# powerswitch.net
KiCad netlist of a schematic drawn in Altium Designer
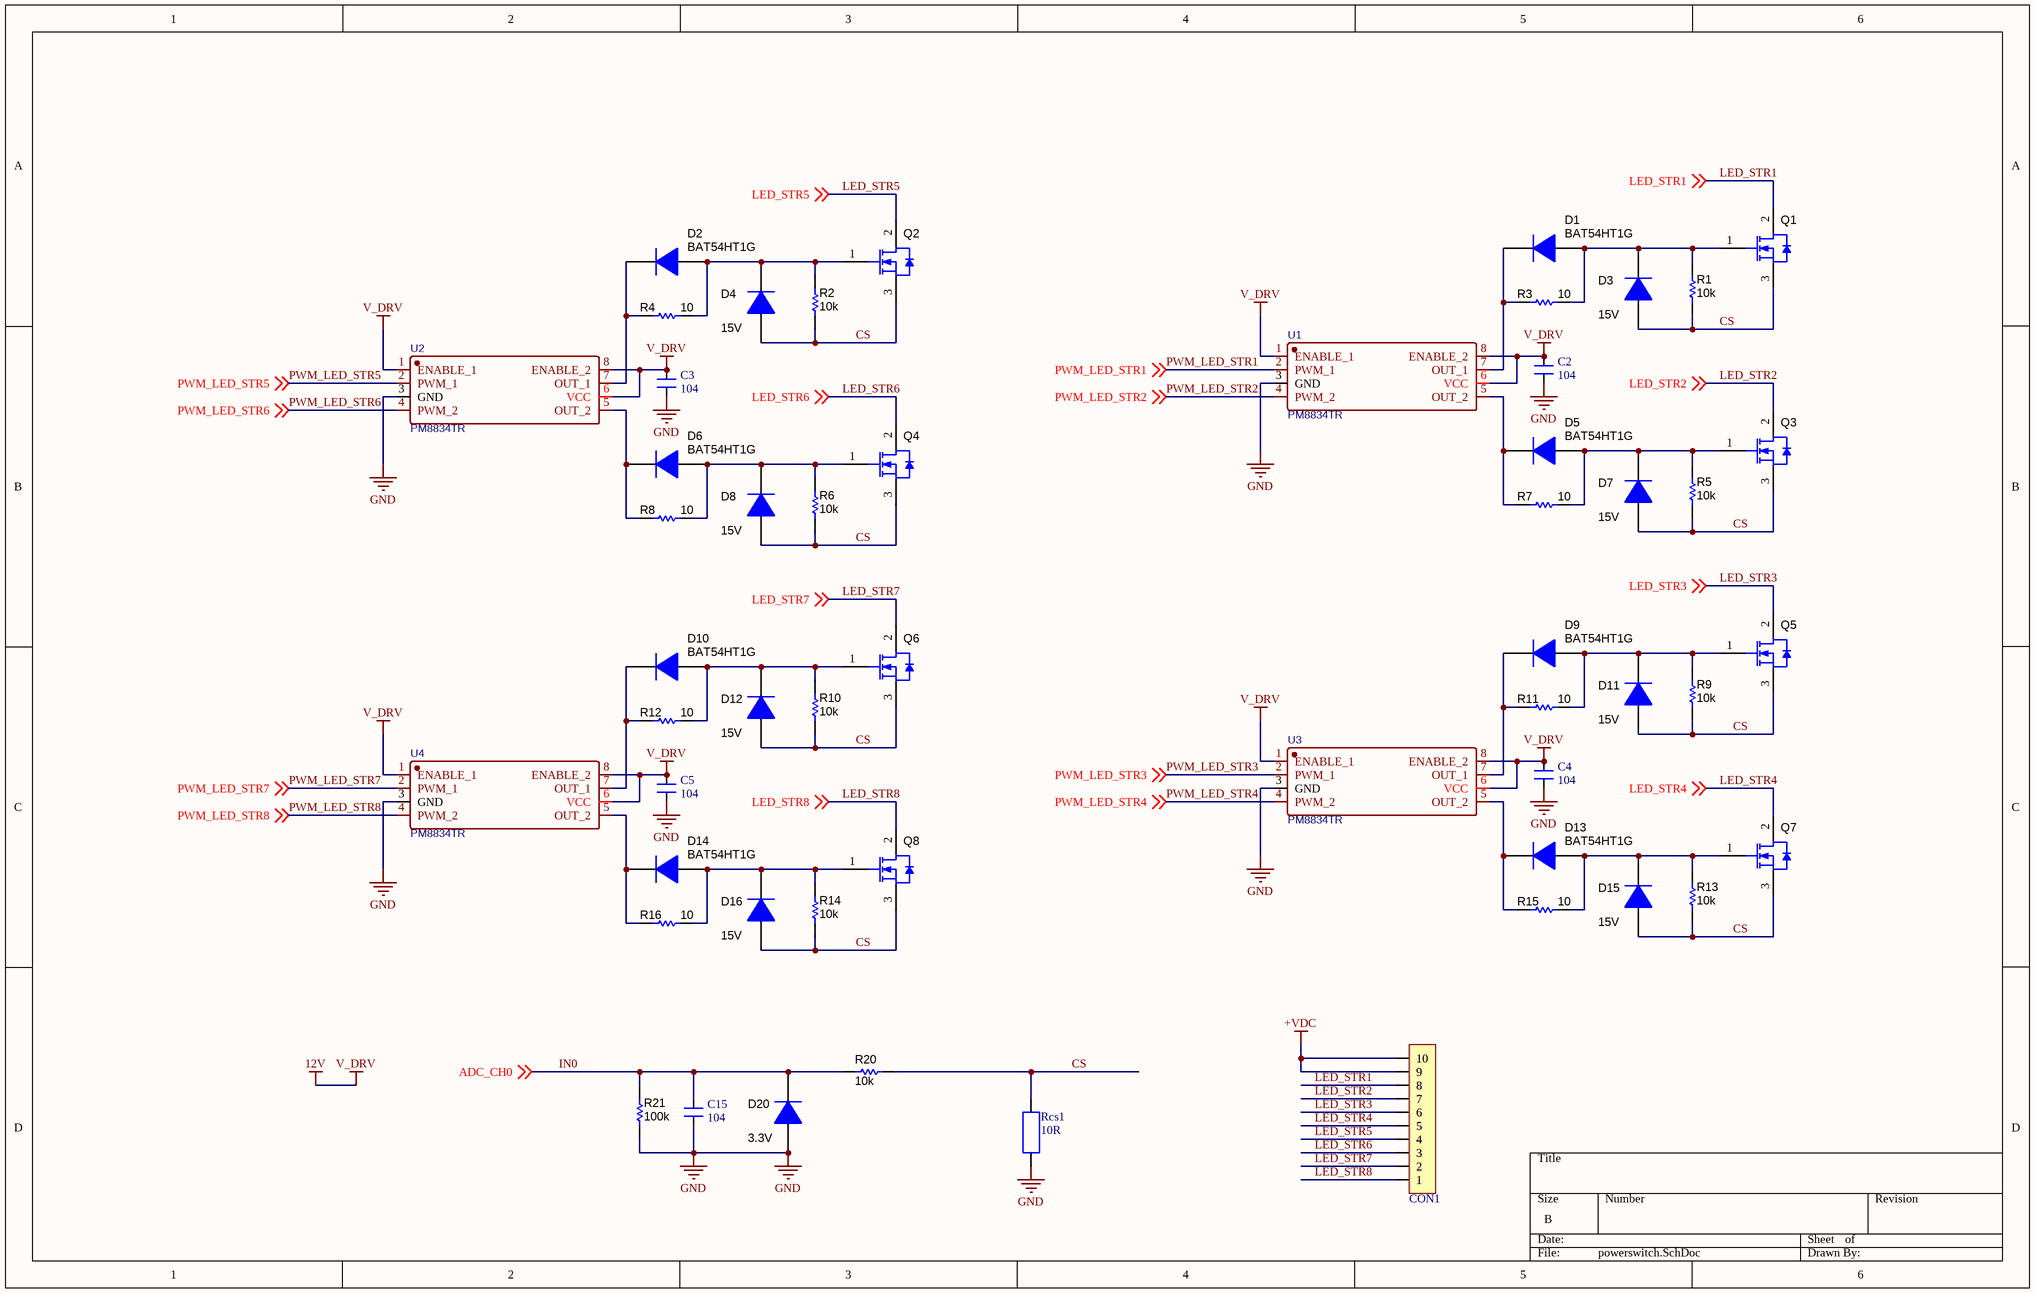
[diagram p0: powerswitch.SchDoc]

(export (version "E")
  (design (tool "Eeschema 10.0.6"))
  (components
    (comp (ref "C2")
      (value "104")
      (footprint "0805_HV")
      (description "Cap SMD")
      (libsource (lib "hatcatbietbay") (part "CM"))
    )
    (comp (ref "C3")
      (value "104")
      (footprint "0805_HV")
      (description "Cap SMD")
      (libsource (lib "hatcatbietbay") (part "CM"))
    )
    (comp (ref "C4")
      (value "104")
      (footprint "0805_HV")
      (description "Cap SMD")
      (libsource (lib "hatcatbietbay") (part "CM"))
    )
    (comp (ref "C5")
      (value "104")
      (footprint "0805_HV")
      (description "Cap SMD")
      (libsource (lib "hatcatbietbay") (part "CM"))
    )
    (comp (ref "C15")
      (value "104")
      (footprint "0805_HV")
      (description "Cap SMD")
      (libsource (lib "hatcatbietbay") (part "CM"))
    )
    (comp (ref "CON1")
      (value "CON 10 EDG 5.08_MH")
      (footprint "Con 10 EDG 5.08")
      (description "CON 10 EDG 5.08 (xanh cong)")
      (libsource (lib "MH_DA_THU_VIEN_16122016") (part "CON 10 EDG 5.08_MH"))
    )
    (comp (ref "D1")
      (value "BAT54HT1G")
      (footprint "SOD-323")
      (description "Diode, Switching, 100 V, 0.2 A, SOD-323")
      (fields
        (field (name "MANUFACTURER") "Micro Commercial Components")
        (field (name "PUBLISHER") "Texas Instruments")
      )
      (libsource (lib "Diode") (part "MMDL914-TP"))
    )
    (comp (ref "D2")
      (value "BAT54HT1G")
      (footprint "SOD-323")
      (description "Diode, Switching, 100 V, 0.2 A, SOD-323")
      (fields
        (field (name "MANUFACTURER") "Micro Commercial Components")
        (field (name "PUBLISHER") "Texas Instruments")
      )
      (libsource (lib "Diode") (part "MMDL914-TP"))
    )
    (comp (ref "D3")
      (value "15V")
      (footprint "SOD-323")
      (description "Diode, Switching, 100 V, 0.2 A, SOD-323")
      (fields
        (field (name "PARTNUMBER") "BAV21W-7-F")
        (field (name "MANUFACTURER") "Micro Commercial Components")
        (field (name "PUBLISHER") "Texas Instruments")
      )
      (libsource (lib "Diode") (part "MMDL914-TP"))
    )
    (comp (ref "D4")
      (value "15V")
      (footprint "SOD-323")
      (description "Diode, Switching, 100 V, 0.2 A, SOD-323")
      (fields
        (field (name "PARTNUMBER") "BAV21W-7-F")
        (field (name "MANUFACTURER") "Micro Commercial Components")
        (field (name "PUBLISHER") "Texas Instruments")
      )
      (libsource (lib "Diode") (part "MMDL914-TP"))
    )
    (comp (ref "D5")
      (value "BAT54HT1G")
      (footprint "SOD-323")
      (description "Diode, Switching, 100 V, 0.2 A, SOD-323")
      (fields
        (field (name "MANUFACTURER") "Micro Commercial Components")
        (field (name "PUBLISHER") "Texas Instruments")
      )
      (libsource (lib "Diode") (part "MMDL914-TP"))
    )
    (comp (ref "D6")
      (value "BAT54HT1G")
      (footprint "SOD-323")
      (description "Diode, Switching, 100 V, 0.2 A, SOD-323")
      (fields
        (field (name "MANUFACTURER") "Micro Commercial Components")
        (field (name "PUBLISHER") "Texas Instruments")
      )
      (libsource (lib "Diode") (part "MMDL914-TP"))
    )
    (comp (ref "D7")
      (value "15V")
      (footprint "SOD-323")
      (description "Diode, Switching, 100 V, 0.2 A, SOD-323")
      (fields
        (field (name "PARTNUMBER") "BAV21W-7-F")
        (field (name "MANUFACTURER") "Micro Commercial Components")
        (field (name "PUBLISHER") "Texas Instruments")
      )
      (libsource (lib "Diode") (part "MMDL914-TP"))
    )
    (comp (ref "D8")
      (value "15V")
      (footprint "SOD-323")
      (description "Diode, Switching, 100 V, 0.2 A, SOD-323")
      (fields
        (field (name "PARTNUMBER") "BAV21W-7-F")
        (field (name "MANUFACTURER") "Micro Commercial Components")
        (field (name "PUBLISHER") "Texas Instruments")
      )
      (libsource (lib "Diode") (part "MMDL914-TP"))
    )
    (comp (ref "D9")
      (value "BAT54HT1G")
      (footprint "SOD-323")
      (description "Diode, Switching, 100 V, 0.2 A, SOD-323")
      (fields
        (field (name "MANUFACTURER") "Micro Commercial Components")
        (field (name "PUBLISHER") "Texas Instruments")
      )
      (libsource (lib "Diode") (part "MMDL914-TP"))
    )
    (comp (ref "D10")
      (value "BAT54HT1G")
      (footprint "SOD-323")
      (description "Diode, Switching, 100 V, 0.2 A, SOD-323")
      (fields
        (field (name "MANUFACTURER") "Micro Commercial Components")
        (field (name "PUBLISHER") "Texas Instruments")
      )
      (libsource (lib "Diode") (part "MMDL914-TP"))
    )
    (comp (ref "D11")
      (value "15V")
      (footprint "SOD-323")
      (description "Diode, Switching, 100 V, 0.2 A, SOD-323")
      (fields
        (field (name "PARTNUMBER") "BAV21W-7-F")
        (field (name "MANUFACTURER") "Micro Commercial Components")
        (field (name "PUBLISHER") "Texas Instruments")
      )
      (libsource (lib "Diode") (part "MMDL914-TP"))
    )
    (comp (ref "D12")
      (value "15V")
      (footprint "SOD-323")
      (description "Diode, Switching, 100 V, 0.2 A, SOD-323")
      (fields
        (field (name "PARTNUMBER") "BAV21W-7-F")
        (field (name "MANUFACTURER") "Micro Commercial Components")
        (field (name "PUBLISHER") "Texas Instruments")
      )
      (libsource (lib "Diode") (part "MMDL914-TP"))
    )
    (comp (ref "D13")
      (value "BAT54HT1G")
      (footprint "SOD-323")
      (description "Diode, Switching, 100 V, 0.2 A, SOD-323")
      (fields
        (field (name "MANUFACTURER") "Micro Commercial Components")
        (field (name "PUBLISHER") "Texas Instruments")
      )
      (libsource (lib "Diode") (part "MMDL914-TP"))
    )
    (comp (ref "D14")
      (value "BAT54HT1G")
      (footprint "SOD-323")
      (description "Diode, Switching, 100 V, 0.2 A, SOD-323")
      (fields
        (field (name "MANUFACTURER") "Micro Commercial Components")
        (field (name "PUBLISHER") "Texas Instruments")
      )
      (libsource (lib "Diode") (part "MMDL914-TP"))
    )
    (comp (ref "D15")
      (value "15V")
      (footprint "SOD-323")
      (description "Diode, Switching, 100 V, 0.2 A, SOD-323")
      (fields
        (field (name "PARTNUMBER") "BAV21W-7-F")
        (field (name "MANUFACTURER") "Micro Commercial Components")
        (field (name "PUBLISHER") "Texas Instruments")
      )
      (libsource (lib "Diode") (part "MMDL914-TP"))
    )
    (comp (ref "D16")
      (value "15V")
      (footprint "SOD-323")
      (description "Diode, Switching, 100 V, 0.2 A, SOD-323")
      (fields
        (field (name "PARTNUMBER") "BAV21W-7-F")
        (field (name "MANUFACTURER") "Micro Commercial Components")
        (field (name "PUBLISHER") "Texas Instruments")
      )
      (libsource (lib "Diode") (part "MMDL914-TP"))
    )
    (comp (ref "D20")
      (value "3.3V")
      (footprint "SOD-323")
      (description "Diode, Switching, 100 V, 0.2 A, SOD-323")
      (fields
        (field (name "PARTNUMBER") "BAV21W-7-F")
        (field (name "MANUFACTURER") "Micro Commercial Components")
        (field (name "PUBLISHER") "Texas Instruments")
      )
      (libsource (lib "Diode") (part "MMDL914-TP"))
    )
    (comp (ref "Q1")
      (value "IPA60R330P")
      (footprint "TO-220AB_NH")
      (description "MOSFET N-CH 600V 10.6A TO220")
      (fields
        (field (name "PARTNUMBER") "IPA60R330P6XKSA1")
        (field (name "MANUFACTURER") "Infineon Technologies")
        (field (name "SYMBOLCREATOR") "x0199378")
      )
      (libsource (lib "Final symbols") (part "IPP60R190P6"))
    )
    (comp (ref "Q2")
      (value "IPA60R330P")
      (footprint "TO-220AB_NH")
      (description "MOSFET N-CH 600V 10.6A TO220")
      (fields
        (field (name "PARTNUMBER") "IPA60R330P6XKSA1")
        (field (name "MANUFACTURER") "Infineon Technologies")
        (field (name "SYMBOLCREATOR") "x0199378")
      )
      (libsource (lib "Final symbols") (part "IPP60R190P6"))
    )
    (comp (ref "Q3")
      (value "IPA60R330P")
      (footprint "TO-220AB_NH")
      (description "MOSFET N-CH 600V 10.6A TO220")
      (fields
        (field (name "PARTNUMBER") "IPA60R330P6XKSA1")
        (field (name "MANUFACTURER") "Infineon Technologies")
        (field (name "SYMBOLCREATOR") "x0199378")
      )
      (libsource (lib "Final symbols") (part "IPP60R190P6"))
    )
    (comp (ref "Q4")
      (value "IPA60R330P")
      (footprint "TO-220AB_NH")
      (description "MOSFET N-CH 600V 10.6A TO220")
      (fields
        (field (name "PARTNUMBER") "IPA60R330P6XKSA1")
        (field (name "MANUFACTURER") "Infineon Technologies")
        (field (name "SYMBOLCREATOR") "x0199378")
      )
      (libsource (lib "Final symbols") (part "IPP60R190P6"))
    )
    (comp (ref "Q5")
      (value "IPA60R330P")
      (footprint "TO-220AB_NH")
      (description "MOSFET N-CH 600V 10.6A TO220")
      (fields
        (field (name "PARTNUMBER") "IPA60R330P6XKSA1")
        (field (name "MANUFACTURER") "Infineon Technologies")
        (field (name "SYMBOLCREATOR") "x0199378")
      )
      (libsource (lib "Final symbols") (part "IPP60R190P6"))
    )
    (comp (ref "Q6")
      (value "IPA60R330P")
      (footprint "TO-220AB_NH")
      (description "MOSFET N-CH 600V 10.6A TO220")
      (fields
        (field (name "PARTNUMBER") "IPA60R330P6XKSA1")
        (field (name "MANUFACTURER") "Infineon Technologies")
        (field (name "SYMBOLCREATOR") "x0199378")
      )
      (libsource (lib "Final symbols") (part "IPP60R190P6"))
    )
    (comp (ref "Q7")
      (value "IPA60R330P")
      (footprint "TO-220AB_NH")
      (description "MOSFET N-CH 600V 10.6A TO220")
      (fields
        (field (name "PARTNUMBER") "IPA60R330P6XKSA1")
        (field (name "MANUFACTURER") "Infineon Technologies")
        (field (name "SYMBOLCREATOR") "x0199378")
      )
      (libsource (lib "Final symbols") (part "IPP60R190P6"))
    )
    (comp (ref "Q8")
      (value "IPA60R330P")
      (footprint "TO-220AB_NH")
      (description "MOSFET N-CH 600V 10.6A TO220")
      (fields
        (field (name "PARTNUMBER") "IPA60R330P6XKSA1")
        (field (name "MANUFACTURER") "Infineon Technologies")
        (field (name "SYMBOLCREATOR") "x0199378")
      )
      (libsource (lib "Final symbols") (part "IPP60R190P6"))
    )
    (comp (ref "R1")
      (value "10k")
      (footprint "Tro SMD 0805")
      (description "RES, 100, 1%, 0.1 W, 0402")
      (fields
        (field (name "PARTNUMBER") "ERJ-2RKF1000X")
        (field (name "MANUFACTURER") "Panasonic")
        (field (name "PUBLISHER") "Texas Instruments")
      )
      (libsource (lib "mySch") (part "R nho"))
    )
    (comp (ref "R2")
      (value "10k")
      (footprint "Tro SMD 0805")
      (description "RES, 100, 1%, 0.1 W, 0402")
      (fields
        (field (name "PARTNUMBER") "ERJ-2RKF1000X")
        (field (name "MANUFACTURER") "Panasonic")
        (field (name "PUBLISHER") "Texas Instruments")
      )
      (libsource (lib "mySch") (part "R nho"))
    )
    (comp (ref "R3")
      (value "10")
      (footprint "Tro SMD 0805")
      (description "RES, 100, 1%, 0.1 W, 0402")
      (fields
        (field (name "PARTNUMBER") "ERJ-2RKF1000X")
        (field (name "MANUFACTURER") "Panasonic")
        (field (name "PUBLISHER") "Texas Instruments")
      )
      (libsource (lib "mySch") (part "R nho"))
    )
    (comp (ref "R4")
      (value "10")
      (footprint "Tro SMD 0805")
      (description "RES, 100, 1%, 0.1 W, 0402")
      (fields
        (field (name "PARTNUMBER") "ERJ-2RKF1000X")
        (field (name "MANUFACTURER") "Panasonic")
        (field (name "PUBLISHER") "Texas Instruments")
      )
      (libsource (lib "mySch") (part "R nho"))
    )
    (comp (ref "R5")
      (value "10k")
      (footprint "Tro SMD 0805")
      (description "RES, 100, 1%, 0.1 W, 0402")
      (fields
        (field (name "PARTNUMBER") "ERJ-2RKF1000X")
        (field (name "MANUFACTURER") "Panasonic")
        (field (name "PUBLISHER") "Texas Instruments")
      )
      (libsource (lib "mySch") (part "R nho"))
    )
    (comp (ref "R6")
      (value "10k")
      (footprint "Tro SMD 0805")
      (description "RES, 100, 1%, 0.1 W, 0402")
      (fields
        (field (name "PARTNUMBER") "ERJ-2RKF1000X")
        (field (name "MANUFACTURER") "Panasonic")
        (field (name "PUBLISHER") "Texas Instruments")
      )
      (libsource (lib "mySch") (part "R nho"))
    )
    (comp (ref "R7")
      (value "10")
      (footprint "Tro SMD 0805")
      (description "RES, 100, 1%, 0.1 W, 0402")
      (fields
        (field (name "PARTNUMBER") "ERJ-2RKF1000X")
        (field (name "MANUFACTURER") "Panasonic")
        (field (name "PUBLISHER") "Texas Instruments")
      )
      (libsource (lib "mySch") (part "R nho"))
    )
    (comp (ref "R8")
      (value "10")
      (footprint "Tro SMD 0805")
      (description "RES, 100, 1%, 0.1 W, 0402")
      (fields
        (field (name "PARTNUMBER") "ERJ-2RKF1000X")
        (field (name "MANUFACTURER") "Panasonic")
        (field (name "PUBLISHER") "Texas Instruments")
      )
      (libsource (lib "mySch") (part "R nho"))
    )
    (comp (ref "R9")
      (value "10k")
      (footprint "Tro SMD 0805")
      (description "RES, 100, 1%, 0.1 W, 0402")
      (fields
        (field (name "PARTNUMBER") "ERJ-2RKF1000X")
        (field (name "MANUFACTURER") "Panasonic")
        (field (name "PUBLISHER") "Texas Instruments")
      )
      (libsource (lib "mySch") (part "R nho"))
    )
    (comp (ref "R10")
      (value "10k")
      (footprint "Tro SMD 0805")
      (description "RES, 100, 1%, 0.1 W, 0402")
      (fields
        (field (name "PARTNUMBER") "ERJ-2RKF1000X")
        (field (name "MANUFACTURER") "Panasonic")
        (field (name "PUBLISHER") "Texas Instruments")
      )
      (libsource (lib "mySch") (part "R nho"))
    )
    (comp (ref "R11")
      (value "10")
      (footprint "Tro SMD 0805")
      (description "RES, 100, 1%, 0.1 W, 0402")
      (fields
        (field (name "PARTNUMBER") "ERJ-2RKF1000X")
        (field (name "MANUFACTURER") "Panasonic")
        (field (name "PUBLISHER") "Texas Instruments")
      )
      (libsource (lib "mySch") (part "R nho"))
    )
    (comp (ref "R12")
      (value "10")
      (footprint "Tro SMD 0805")
      (description "RES, 100, 1%, 0.1 W, 0402")
      (fields
        (field (name "PARTNUMBER") "ERJ-2RKF1000X")
        (field (name "MANUFACTURER") "Panasonic")
        (field (name "PUBLISHER") "Texas Instruments")
      )
      (libsource (lib "mySch") (part "R nho"))
    )
    (comp (ref "R13")
      (value "10k")
      (footprint "Tro SMD 0805")
      (description "RES, 100, 1%, 0.1 W, 0402")
      (fields
        (field (name "PARTNUMBER") "ERJ-2RKF1000X")
        (field (name "MANUFACTURER") "Panasonic")
        (field (name "PUBLISHER") "Texas Instruments")
      )
      (libsource (lib "mySch") (part "R nho"))
    )
    (comp (ref "R14")
      (value "10k")
      (footprint "Tro SMD 0805")
      (description "RES, 100, 1%, 0.1 W, 0402")
      (fields
        (field (name "PARTNUMBER") "ERJ-2RKF1000X")
        (field (name "MANUFACTURER") "Panasonic")
        (field (name "PUBLISHER") "Texas Instruments")
      )
      (libsource (lib "mySch") (part "R nho"))
    )
    (comp (ref "R15")
      (value "10")
      (footprint "Tro SMD 0805")
      (description "RES, 100, 1%, 0.1 W, 0402")
      (fields
        (field (name "PARTNUMBER") "ERJ-2RKF1000X")
        (field (name "MANUFACTURER") "Panasonic")
        (field (name "PUBLISHER") "Texas Instruments")
      )
      (libsource (lib "mySch") (part "R nho"))
    )
    (comp (ref "R16")
      (value "10")
      (footprint "Tro SMD 0805")
      (description "RES, 100, 1%, 0.1 W, 0402")
      (fields
        (field (name "PARTNUMBER") "ERJ-2RKF1000X")
        (field (name "MANUFACTURER") "Panasonic")
        (field (name "PUBLISHER") "Texas Instruments")
      )
      (libsource (lib "mySch") (part "R nho"))
    )
    (comp (ref "R20")
      (value "10k")
      (footprint "Tro SMD 0805")
      (description "RES, 100, 1%, 0.1 W, 0402")
      (fields
        (field (name "PARTNUMBER") "ERJ-2RKF1000X")
        (field (name "MANUFACTURER") "Panasonic")
        (field (name "PUBLISHER") "Texas Instruments")
      )
      (libsource (lib "mySch") (part "R nho"))
    )
    (comp (ref "R21")
      (value "100k")
      (footprint "Tro SMD 0805")
      (description "RES, 100, 1%, 0.1 W, 0402")
      (fields
        (field (name "PARTNUMBER") "ERJ-2RKF1000X")
        (field (name "MANUFACTURER") "Panasonic")
        (field (name "PUBLISHER") "Texas Instruments")
      )
      (libsource (lib "mySch") (part "R nho"))
    )
    (comp (ref "Rcs1")
      (value "10R")
      (footprint "TRO_VACH_2W")
      (libsource (lib "MH_DA_THU_VIEN_16122016") (part "TRO_CS_2W_MH"))
    )
    (comp (ref "U1")
      (value "PM8834TR")
      (footprint "SOP 8")
      (fields (field (name "BOM_SUPPLIER PART") "C221495") (field (name "CONTRIBUTOR") "LCSC"))
      (libsource (lib "Schlib1") (part "PM8834TR"))
    )
    (comp (ref "U2")
      (value "PM8834TR")
      (footprint "SOP 8")
      (fields (field (name "BOM_SUPPLIER PART") "C221495") (field (name "CONTRIBUTOR") "LCSC"))
      (libsource (lib "Schlib1") (part "PM8834TR"))
    )
    (comp (ref "U3")
      (value "PM8834TR")
      (footprint "SOP 8")
      (fields (field (name "BOM_SUPPLIER PART") "C221495") (field (name "CONTRIBUTOR") "LCSC"))
      (libsource (lib "Schlib1") (part "PM8834TR"))
    )
    (comp (ref "U4")
      (value "PM8834TR")
      (footprint "SOP 8")
      (fields (field (name "BOM_SUPPLIER PART") "C221495") (field (name "CONTRIBUTOR") "LCSC"))
      (libsource (lib "Schlib1") (part "PM8834TR"))
    )
  )
  (nets
    (net (code "1") (name "+VDC") (class "Default")
      (node (ref "CON1") (pin "10") (pinfunction "10_10") (pintype "passive"))
      (node (ref "CON1") (pin "9") (pinfunction "9_9") (pintype "passive"))
    )
    (net (code "2") (name "/CS") (class "Default")
      (node (ref "D11") (pin "2") (pinfunction "A_2") (pintype "passive"))
      (node (ref "D12") (pin "2") (pinfunction "A_2") (pintype "passive"))
      (node (ref "D15") (pin "2") (pinfunction "A_2") (pintype "passive"))
      (node (ref "D16") (pin "2") (pinfunction "A_2") (pintype "passive"))
      (node (ref "D3") (pin "2") (pinfunction "A_2") (pintype "passive"))
      (node (ref "D4") (pin "2") (pinfunction "A_2") (pintype "passive"))
      (node (ref "D7") (pin "2") (pinfunction "A_2") (pintype "passive"))
      (node (ref "D8") (pin "2") (pinfunction "A_2") (pintype "passive"))
      (node (ref "Q1") (pin "3") (pinfunction "S_3") (pintype "passive"))
      (node (ref "Q2") (pin "3") (pinfunction "S_3") (pintype "passive"))
      (node (ref "Q3") (pin "3") (pinfunction "S_3") (pintype "passive"))
      (node (ref "Q4") (pin "3") (pinfunction "S_3") (pintype "passive"))
      (node (ref "Q5") (pin "3") (pinfunction "S_3") (pintype "passive"))
      (node (ref "Q6") (pin "3") (pinfunction "S_3") (pintype "passive"))
      (node (ref "Q7") (pin "3") (pinfunction "S_3") (pintype "passive"))
      (node (ref "Q8") (pin "3") (pinfunction "S_3") (pintype "passive"))
      (node (ref "R1") (pin "2") (pinfunction "2_2") (pintype "passive"))
      (node (ref "R10") (pin "2") (pinfunction "2_2") (pintype "passive"))
      (node (ref "R13") (pin "2") (pinfunction "2_2") (pintype "passive"))
      (node (ref "R14") (pin "2") (pinfunction "2_2") (pintype "passive"))
      (node (ref "R2") (pin "2") (pinfunction "2_2") (pintype "passive"))
      (node (ref "R20") (pin "2") (pinfunction "2_2") (pintype "passive"))
      (node (ref "R5") (pin "2") (pinfunction "2_2") (pintype "passive"))
      (node (ref "R6") (pin "2") (pinfunction "2_2") (pintype "passive"))
      (node (ref "R9") (pin "2") (pinfunction "2_2") (pintype "passive"))
      (node (ref "Rcs1") (pin "2") (pinfunction "2_2") (pintype "passive"))
    )
    (net (code "3") (name "12V") (class "Default")
      (node (ref "C2") (pin "2") (pinfunction "2_2") (pintype "passive"))
      (node (ref "C3") (pin "2") (pinfunction "2_2") (pintype "passive"))
      (node (ref "C4") (pin "2") (pinfunction "2_2") (pintype "passive"))
      (node (ref "C5") (pin "2") (pinfunction "2_2") (pintype "passive"))
      (node (ref "U1") (pin "1") (pinfunction "ENABLE_1_1") (pintype "passive"))
      (node (ref "U1") (pin "6") (pinfunction "VCC_6") (pintype "passive"))
      (node (ref "U1") (pin "8") (pinfunction "ENABLE_2_8") (pintype "passive"))
      (node (ref "U2") (pin "1") (pinfunction "ENABLE_1_1") (pintype "passive"))
      (node (ref "U2") (pin "6") (pinfunction "VCC_6") (pintype "passive"))
      (node (ref "U2") (pin "8") (pinfunction "ENABLE_2_8") (pintype "passive"))
      (node (ref "U3") (pin "1") (pinfunction "ENABLE_1_1") (pintype "passive"))
      (node (ref "U3") (pin "6") (pinfunction "VCC_6") (pintype "passive"))
      (node (ref "U3") (pin "8") (pinfunction "ENABLE_2_8") (pintype "passive"))
      (node (ref "U4") (pin "1") (pinfunction "ENABLE_1_1") (pintype "passive"))
      (node (ref "U4") (pin "6") (pinfunction "VCC_6") (pintype "passive"))
      (node (ref "U4") (pin "8") (pinfunction "ENABLE_2_8") (pintype "passive"))
    )
    (net (code "4") (name "ADC_CH0") (class "Default")
      (node (ref "C15") (pin "2") (pinfunction "2_2") (pintype "passive"))
      (node (ref "D20") (pin "1") (pinfunction "K_1") (pintype "passive"))
      (node (ref "R20") (pin "1") (pinfunction "1_1") (pintype "passive"))
      (node (ref "R21") (pin "1") (pinfunction "1_1") (pintype "passive"))
    )
    (net (code "5") (name "GND") (class "Default")
      (node (ref "C15") (pin "1") (pinfunction "1_1") (pintype "passive"))
      (node (ref "C2") (pin "1") (pinfunction "1_1") (pintype "passive"))
      (node (ref "C3") (pin "1") (pinfunction "1_1") (pintype "passive"))
      (node (ref "C4") (pin "1") (pinfunction "1_1") (pintype "passive"))
      (node (ref "C5") (pin "1") (pinfunction "1_1") (pintype "passive"))
      (node (ref "D20") (pin "2") (pinfunction "A_2") (pintype "passive"))
      (node (ref "R21") (pin "2") (pinfunction "2_2") (pintype "passive"))
      (node (ref "Rcs1") (pin "1") (pinfunction "1_1") (pintype "passive"))
      (node (ref "U1") (pin "3") (pinfunction "GND_3") (pintype "passive"))
      (node (ref "U2") (pin "3") (pinfunction "GND_3") (pintype "passive"))
      (node (ref "U3") (pin "3") (pinfunction "GND_3") (pintype "passive"))
      (node (ref "U4") (pin "3") (pinfunction "GND_3") (pintype "passive"))
    )
    (net (code "6") (name "LED_STR1") (class "Default")
      (node (ref "CON1") (pin "8") (pinfunction "8_8") (pintype "passive"))
      (node (ref "Q1") (pin "2") (pinfunction "D_2") (pintype "passive"))
    )
    (net (code "7") (name "LED_STR2") (class "Default")
      (node (ref "CON1") (pin "7") (pinfunction "7_7") (pintype "passive"))
      (node (ref "Q3") (pin "2") (pinfunction "D_2") (pintype "passive"))
    )
    (net (code "8") (name "LED_STR3") (class "Default")
      (node (ref "CON1") (pin "6") (pinfunction "6_6") (pintype "passive"))
      (node (ref "Q5") (pin "2") (pinfunction "D_2") (pintype "passive"))
    )
    (net (code "9") (name "LED_STR4") (class "Default")
      (node (ref "CON1") (pin "5") (pinfunction "5_5") (pintype "passive"))
      (node (ref "Q7") (pin "2") (pinfunction "D_2") (pintype "passive"))
    )
    (net (code "10") (name "LED_STR5") (class "Default")
      (node (ref "CON1") (pin "4") (pinfunction "4_4") (pintype "passive"))
      (node (ref "Q2") (pin "2") (pinfunction "D_2") (pintype "passive"))
    )
    (net (code "11") (name "LED_STR6") (class "Default")
      (node (ref "CON1") (pin "3") (pinfunction "3_3") (pintype "passive"))
      (node (ref "Q4") (pin "2") (pinfunction "D_2") (pintype "passive"))
    )
    (net (code "12") (name "LED_STR7") (class "Default")
      (node (ref "CON1") (pin "2") (pinfunction "2_2") (pintype "passive"))
      (node (ref "Q6") (pin "2") (pinfunction "D_2") (pintype "passive"))
    )
    (net (code "13") (name "LED_STR8") (class "Default")
      (node (ref "CON1") (pin "1") (pinfunction "1_1") (pintype "passive"))
      (node (ref "Q8") (pin "2") (pinfunction "D_2") (pintype "passive"))
    )
    (net (code "14") (name "Net-(D1-A)") (class "Default")
      (node (ref "D1") (pin "2") (pinfunction "A_2") (pintype "passive"))
      (node (ref "D3") (pin "1") (pinfunction "K_1") (pintype "passive"))
      (node (ref "Q1") (pin "1") (pinfunction "G_1") (pintype "passive"))
      (node (ref "R1") (pin "1") (pinfunction "1_1") (pintype "passive"))
      (node (ref "R3") (pin "1") (pinfunction "1_1") (pintype "passive"))
    )
    (net (code "15") (name "Net-(D1-K)") (class "Default")
      (node (ref "D1") (pin "1") (pinfunction "K_1") (pintype "passive"))
      (node (ref "R3") (pin "2") (pinfunction "2_2") (pintype "passive"))
      (node (ref "U1") (pin "7") (pinfunction "OUT_1_7") (pintype "passive"))
    )
    (net (code "16") (name "Net-(D2-A)") (class "Default")
      (node (ref "D2") (pin "2") (pinfunction "A_2") (pintype "passive"))
      (node (ref "D4") (pin "1") (pinfunction "K_1") (pintype "passive"))
      (node (ref "Q2") (pin "1") (pinfunction "G_1") (pintype "passive"))
      (node (ref "R2") (pin "1") (pinfunction "1_1") (pintype "passive"))
      (node (ref "R4") (pin "1") (pinfunction "1_1") (pintype "passive"))
    )
    (net (code "17") (name "Net-(D2-K)") (class "Default")
      (node (ref "D2") (pin "1") (pinfunction "K_1") (pintype "passive"))
      (node (ref "R4") (pin "2") (pinfunction "2_2") (pintype "passive"))
      (node (ref "U2") (pin "7") (pinfunction "OUT_1_7") (pintype "passive"))
    )
    (net (code "18") (name "Net-(D5-A)") (class "Default")
      (node (ref "D5") (pin "2") (pinfunction "A_2") (pintype "passive"))
      (node (ref "D7") (pin "1") (pinfunction "K_1") (pintype "passive"))
      (node (ref "Q3") (pin "1") (pinfunction "G_1") (pintype "passive"))
      (node (ref "R5") (pin "1") (pinfunction "1_1") (pintype "passive"))
      (node (ref "R7") (pin "1") (pinfunction "1_1") (pintype "passive"))
    )
    (net (code "19") (name "Net-(D5-K)") (class "Default")
      (node (ref "D5") (pin "1") (pinfunction "K_1") (pintype "passive"))
      (node (ref "R7") (pin "2") (pinfunction "2_2") (pintype "passive"))
      (node (ref "U1") (pin "5") (pinfunction "OUT_2_5") (pintype "passive"))
    )
    (net (code "20") (name "Net-(D6-A)") (class "Default")
      (node (ref "D6") (pin "2") (pinfunction "A_2") (pintype "passive"))
      (node (ref "D8") (pin "1") (pinfunction "K_1") (pintype "passive"))
      (node (ref "Q4") (pin "1") (pinfunction "G_1") (pintype "passive"))
      (node (ref "R6") (pin "1") (pinfunction "1_1") (pintype "passive"))
      (node (ref "R8") (pin "1") (pinfunction "1_1") (pintype "passive"))
    )
    (net (code "21") (name "Net-(D6-K)") (class "Default")
      (node (ref "D6") (pin "1") (pinfunction "K_1") (pintype "passive"))
      (node (ref "R8") (pin "2") (pinfunction "2_2") (pintype "passive"))
      (node (ref "U2") (pin "5") (pinfunction "OUT_2_5") (pintype "passive"))
    )
    (net (code "22") (name "Net-(D9-K)") (class "Default")
      (node (ref "D9") (pin "1") (pinfunction "K_1") (pintype "passive"))
      (node (ref "R11") (pin "2") (pinfunction "2_2") (pintype "passive"))
      (node (ref "U3") (pin "7") (pinfunction "OUT_1_7") (pintype "passive"))
    )
    (net (code "23") (name "Net-(D10-A)") (class "Default")
      (node (ref "D10") (pin "2") (pinfunction "A_2") (pintype "passive"))
      (node (ref "D12") (pin "1") (pinfunction "K_1") (pintype "passive"))
      (node (ref "Q6") (pin "1") (pinfunction "G_1") (pintype "passive"))
      (node (ref "R10") (pin "1") (pinfunction "1_1") (pintype "passive"))
      (node (ref "R12") (pin "1") (pinfunction "1_1") (pintype "passive"))
    )
    (net (code "24") (name "Net-(D10-K)") (class "Default")
      (node (ref "D10") (pin "1") (pinfunction "K_1") (pintype "passive"))
      (node (ref "R12") (pin "2") (pinfunction "2_2") (pintype "passive"))
      (node (ref "U4") (pin "7") (pinfunction "OUT_1_7") (pintype "passive"))
    )
    (net (code "25") (name "Net-(D11-K)") (class "Default")
      (node (ref "D11") (pin "1") (pinfunction "K_1") (pintype "passive"))
      (node (ref "D9") (pin "2") (pinfunction "A_2") (pintype "passive"))
      (node (ref "Q5") (pin "1") (pinfunction "G_1") (pintype "passive"))
      (node (ref "R11") (pin "1") (pinfunction "1_1") (pintype "passive"))
      (node (ref "R9") (pin "1") (pinfunction "1_1") (pintype "passive"))
    )
    (net (code "26") (name "Net-(D13-A)") (class "Default")
      (node (ref "D13") (pin "2") (pinfunction "A_2") (pintype "passive"))
      (node (ref "D15") (pin "1") (pinfunction "K_1") (pintype "passive"))
      (node (ref "Q7") (pin "1") (pinfunction "G_1") (pintype "passive"))
      (node (ref "R13") (pin "1") (pinfunction "1_1") (pintype "passive"))
      (node (ref "R15") (pin "1") (pinfunction "1_1") (pintype "passive"))
    )
    (net (code "27") (name "Net-(D13-K)") (class "Default")
      (node (ref "D13") (pin "1") (pinfunction "K_1") (pintype "passive"))
      (node (ref "R15") (pin "2") (pinfunction "2_2") (pintype "passive"))
      (node (ref "U3") (pin "5") (pinfunction "OUT_2_5") (pintype "passive"))
    )
    (net (code "28") (name "Net-(D14-A)") (class "Default")
      (node (ref "D14") (pin "2") (pinfunction "A_2") (pintype "passive"))
      (node (ref "D16") (pin "1") (pinfunction "K_1") (pintype "passive"))
      (node (ref "Q8") (pin "1") (pinfunction "G_1") (pintype "passive"))
      (node (ref "R14") (pin "1") (pinfunction "1_1") (pintype "passive"))
      (node (ref "R16") (pin "1") (pinfunction "1_1") (pintype "passive"))
    )
    (net (code "29") (name "Net-(D14-K)") (class "Default")
      (node (ref "D14") (pin "1") (pinfunction "K_1") (pintype "passive"))
      (node (ref "R16") (pin "2") (pinfunction "2_2") (pintype "passive"))
      (node (ref "U4") (pin "5") (pinfunction "OUT_2_5") (pintype "passive"))
    )
    (net (code "30") (name "PWM_LED_STR1") (class "Default")
      (node (ref "U1") (pin "2") (pinfunction "PWM_1_2") (pintype "passive"))
    )
    (net (code "31") (name "PWM_LED_STR2") (class "Default")
      (node (ref "U1") (pin "4") (pinfunction "PWM_2_4") (pintype "passive"))
    )
    (net (code "32") (name "PWM_LED_STR3") (class "Default")
      (node (ref "U3") (pin "2") (pinfunction "PWM_1_2") (pintype "passive"))
    )
    (net (code "33") (name "PWM_LED_STR4") (class "Default")
      (node (ref "U3") (pin "4") (pinfunction "PWM_2_4") (pintype "passive"))
    )
    (net (code "34") (name "PWM_LED_STR5") (class "Default")
      (node (ref "U2") (pin "2") (pinfunction "PWM_1_2") (pintype "passive"))
    )
    (net (code "35") (name "PWM_LED_STR6") (class "Default")
      (node (ref "U2") (pin "4") (pinfunction "PWM_2_4") (pintype "passive"))
    )
    (net (code "36") (name "PWM_LED_STR7") (class "Default")
      (node (ref "U4") (pin "2") (pinfunction "PWM_1_2") (pintype "passive"))
    )
    (net (code "37") (name "PWM_LED_STR8") (class "Default")
      (node (ref "U4") (pin "4") (pinfunction "PWM_2_4") (pintype "passive"))
    )
  )
)
